# AugmentedStethoscope_v4.net
KiCad netlist of a schematic drawn in EAGLE
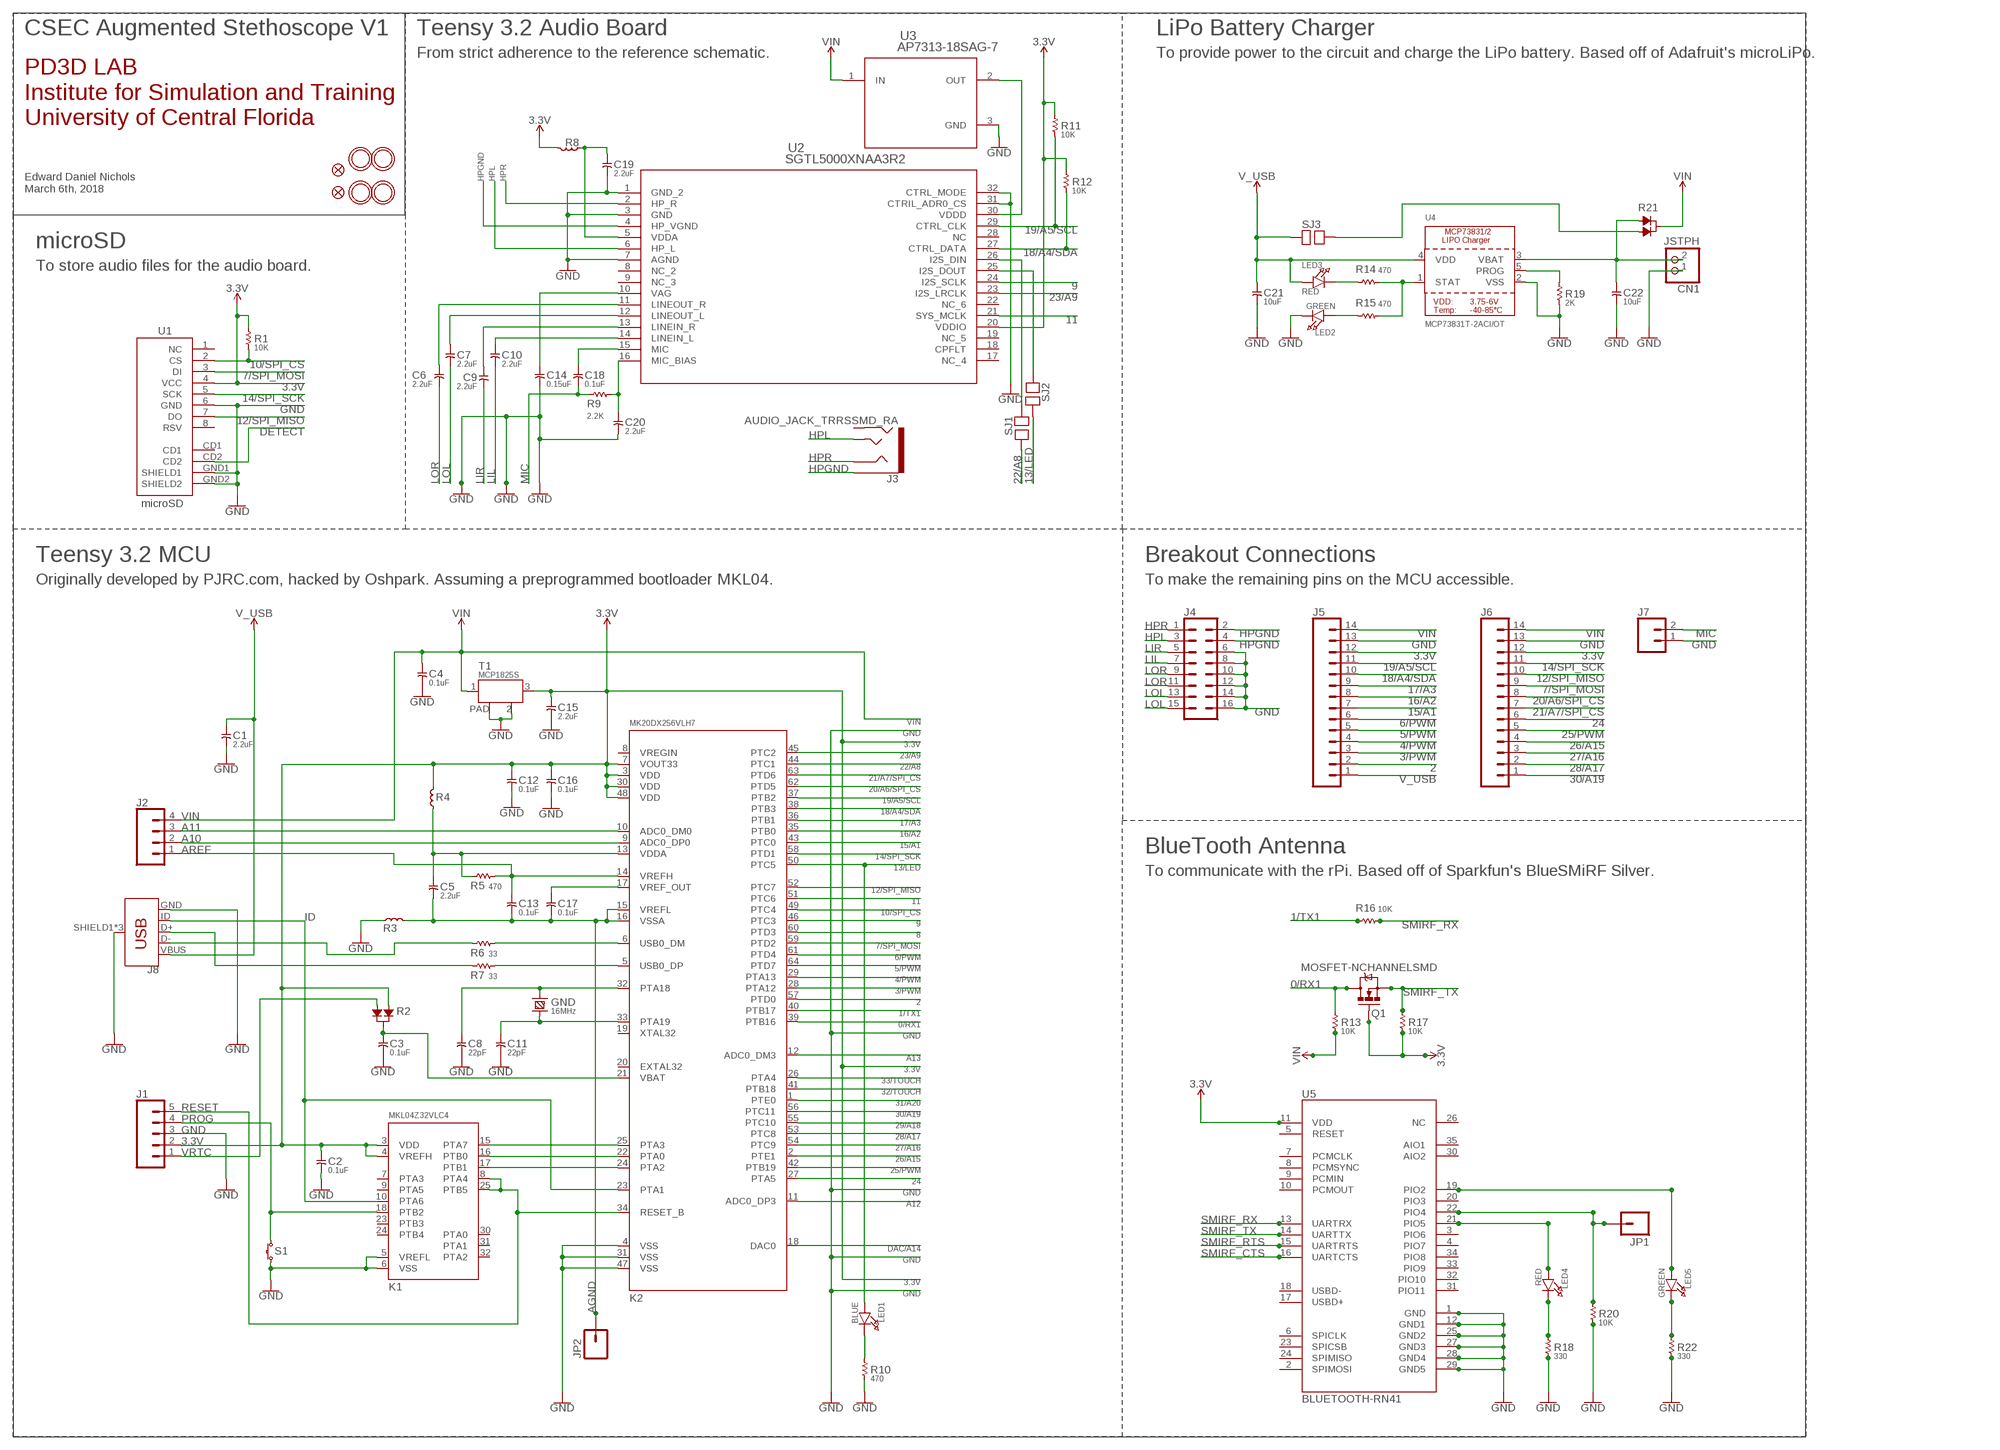
[diagram p0: schematic, sheet 1]

(export (version "E")
  (design (tool "Eeschema 10.0.6"))
  (components
    (comp (ref "C1")
      (value "2.2uF")
      (footprint "eagle-import:C0805")
      (fields (field (name "MF") "Taiyo Yuden") (field (name "MPN") "TMK212B7225KG-TR"))
      (libsource (lib "eagle-import") (part "CAPACITOR-2.2UF"))
    )
    (comp (ref "C2")
      (value "0.1uF")
      (footprint "eagle-import:C0603")
      (fields (field (name "MF") "Murata Electronics") (field (name "MPN") "GRM188R71C104KA01D"))
      (libsource (lib "eagle-import") (part "CAPACITOR-0.1UF"))
    )
    (comp (ref "C3")
      (value "0.1uF")
      (footprint "eagle-import:C0603")
      (fields (field (name "MF") "Murata Electronics") (field (name "MPN") "GRM188R71C104KA01D"))
      (libsource (lib "eagle-import") (part "CAPACITOR-0.1UF"))
    )
    (comp (ref "C4")
      (value "0.1uF")
      (footprint "eagle-import:C0603")
      (fields (field (name "MF") "Murata Electronics") (field (name "MPN") "GRM188R71C104KA01D"))
      (libsource (lib "eagle-import") (part "CAPACITOR-0.1UF"))
    )
    (comp (ref "C5")
      (value "2.2uF")
      (footprint "eagle-import:C0805")
      (fields (field (name "MF") "Taiyo Yuden") (field (name "MPN") "TMK212B7225KG-TR"))
      (libsource (lib "eagle-import") (part "CAPACITOR-2.2UF"))
    )
    (comp (ref "C6")
      (value "2.2uF")
      (footprint "eagle-import:C0805")
      (fields (field (name "MF") "Taiyo Yuden") (field (name "MPN") "TMK212B7225KG-TR"))
      (libsource (lib "eagle-import") (part "CAPACITOR-2.2UF"))
    )
    (comp (ref "C7")
      (value "2.2uF")
      (footprint "eagle-import:C0805")
      (fields (field (name "MF") "Taiyo Yuden") (field (name "MPN") "TMK212B7225KG-TR"))
      (libsource (lib "eagle-import") (part "CAPACITOR-2.2UF"))
    )
    (comp (ref "C8")
      (value "22pF")
      (footprint "eagle-import:C0603")
      (fields (field (name "MF") "Vishay / Vitramon") (field (name "MPN") "VJ0603A220JXACW1BC"))
      (libsource (lib "eagle-import") (part "CAPACITOR-22PF"))
    )
    (comp (ref "C9")
      (value "2.2uF")
      (footprint "eagle-import:C0805")
      (fields (field (name "MF") "Taiyo Yuden") (field (name "MPN") "TMK212B7225KG-TR"))
      (libsource (lib "eagle-import") (part "CAPACITOR-2.2UF"))
    )
    (comp (ref "C10")
      (value "2.2uF")
      (footprint "eagle-import:C0805")
      (fields (field (name "MF") "Taiyo Yuden") (field (name "MPN") "TMK212B7225KG-TR"))
      (libsource (lib "eagle-import") (part "CAPACITOR-2.2UF"))
    )
    (comp (ref "C11")
      (value "22pF")
      (footprint "eagle-import:C0603")
      (fields (field (name "MF") "Vishay / Vitramon") (field (name "MPN") "VJ0603A220JXACW1BC"))
      (libsource (lib "eagle-import") (part "CAPACITOR-22PF"))
    )
    (comp (ref "C12")
      (value "0.1uF")
      (footprint "eagle-import:C0603")
      (fields (field (name "MF") "Murata Electronics") (field (name "MPN") "GRM188R71C104KA01D"))
      (libsource (lib "eagle-import") (part "CAPACITOR-0.1UF"))
    )
    (comp (ref "C13")
      (value "0.1uF")
      (footprint "eagle-import:C0603")
      (fields (field (name "MF") "Murata Electronics") (field (name "MPN") "GRM188R71C104KA01D"))
      (libsource (lib "eagle-import") (part "CAPACITOR-0.1UF"))
    )
    (comp (ref "C14")
      (value "0.15uF")
      (footprint "eagle-import:C0805")
      (fields (field (name "MF") "Taiyo Yuden") (field (name "MPN") "TMK212B7225KG-TR"))
      (libsource (lib "eagle-import") (part "CAPACITOR-2.2UF"))
    )
    (comp (ref "C15")
      (value "2.2uF")
      (footprint "eagle-import:C0805")
      (fields (field (name "MF") "Taiyo Yuden") (field (name "MPN") "TMK212B7225KG-TR"))
      (libsource (lib "eagle-import") (part "CAPACITOR-2.2UF"))
    )
    (comp (ref "C16")
      (value "0.1uF")
      (footprint "eagle-import:C0603")
      (fields (field (name "MF") "Murata Electronics") (field (name "MPN") "GRM188R71C104KA01D"))
      (libsource (lib "eagle-import") (part "CAPACITOR-0.1UF"))
    )
    (comp (ref "C17")
      (value "0.1uF")
      (footprint "eagle-import:C0603")
      (fields (field (name "MF") "Murata Electronics") (field (name "MPN") "GRM188R71C104KA01D"))
      (libsource (lib "eagle-import") (part "CAPACITOR-0.1UF"))
    )
    (comp (ref "C18")
      (value "0.1uF")
      (footprint "eagle-import:C0805")
      (fields (field (name "MF") "Taiyo Yuden") (field (name "MPN") "TMK212B7225KG-TR"))
      (libsource (lib "eagle-import") (part "CAPACITOR-2.2UF"))
    )
    (comp (ref "C19")
      (value "2.2uF")
      (footprint "eagle-import:C0805")
      (fields (field (name "MF") "Taiyo Yuden") (field (name "MPN") "TMK212B7225KG-TR"))
      (libsource (lib "eagle-import") (part "CAPACITOR-2.2UF"))
    )
    (comp (ref "C20")
      (value "2.2uF")
      (footprint "eagle-import:C0805")
      (fields (field (name "MF") "Taiyo Yuden") (field (name "MPN") "TMK212B7225KG-TR"))
      (libsource (lib "eagle-import") (part "CAPACITOR-2.2UF"))
    )
    (comp (ref "C21")
      (value "10uF")
      (footprint "eagle-import:C0603")
      (fields (field (name "MF") "Murata Electronics") (field (name "MPN") "GRM188R71C104KA01D"))
      (libsource (lib "eagle-import") (part "CAPACITOR-0.1UF"))
    )
    (comp (ref "C22")
      (value "10uF")
      (footprint "eagle-import:C0603")
      (fields (field (name "MF") "Murata Electronics") (field (name "MPN") "GRM188R71C104KA01D"))
      (libsource (lib "eagle-import") (part "CAPACITOR-0.1UF"))
    )
    (comp (ref "CN1")
      (value "JSTPH")
      (footprint "eagle-import:JSTPH2")
      (libsource (lib "eagle-import") (part "JST_2PIN"))
    )
    (comp (ref "FID2")
      (value "FIDUCIAL\"\"")
      (footprint "eagle-import:FIDUCIAL_1MM")
      (libsource (lib "eagle-import") (part "FIDUCIAL{dblquote}{dblquote}"))
    )
    (comp (ref "FID3")
      (value "FIDUCIAL\"\"")
      (footprint "eagle-import:FIDUCIAL_1MM")
      (fields (field (name "BOM") "EXCLUDE"))
      (libsource (lib "eagle-import") (part "FIDUCIAL{dblquote}{dblquote}"))
    )
    (comp (ref "GND")
      (value "16MHz")
      (footprint "eagle-import:HC49US")
      (fields (field (name "MF") "ABRACON") (field (name "MPN") "ABL-16.000MHz-B1U"))
      (libsource (lib "eagle-import") (part "CRYSTAL-HC49US"))
    )
    (comp (ref "J1")
      (value "CONN_05")
      (footprint "eagle-import:1X05")
      (libsource (lib "eagle-import") (part "CONN_05"))
    )
    (comp (ref "J2")
      (value "CONN_04")
      (footprint "eagle-import:1X04")
      (libsource (lib "eagle-import") (part "CONN_04"))
    )
    (comp (ref "J3")
      (value "AUDIO_JACK_TRRSSMD_RA")
      (footprint "eagle-import:AUDIO_JACK_3.5MM_TRRS_SMD_RA")
      (libsource (lib "eagle-import") (part "AUDIO_JACK_TRRSSMD_RA"))
    )
    (comp (ref "J4")
      (value "CONN_08X2")
      (footprint "eagle-import:2X8")
      (libsource (lib "eagle-import") (part "CONN_08X2"))
    )
    (comp (ref "J5")
      (value "CONN_14")
      (footprint "eagle-import:1X14")
      (libsource (lib "eagle-import") (part "CONN_14"))
    )
    (comp (ref "J6")
      (value "CONN_14")
      (footprint "eagle-import:1X14")
      (libsource (lib "eagle-import") (part "CONN_14"))
    )
    (comp (ref "J7")
      (value "CONN_02")
      (footprint "eagle-import:1X02")
      (libsource (lib "eagle-import") (part "CONN_02"))
    )
    (comp (ref "J8")
      (value "USB_MICRO-B_FEMALE-SMT")
      (footprint "eagle-import:USB-B-MICRO-SMD")
      (libsource (lib "eagle-import") (part "USB_MICRO-B_FEMALE-SMT"))
    )
    (comp (ref "JP1")
      (value "M01SMDNS")
      (footprint "eagle-import:1X01NS")
      (libsource (lib "eagle-import") (part "M01SMDNS"))
    )
    (comp (ref "JP2")
      (value "M01SMDNS")
      (footprint "eagle-import:1X01NS")
      (libsource (lib "eagle-import") (part "M01SMDNS"))
    )
    (comp (ref "K1")
      (value "MKL04Z32VLC4")
      (footprint "eagle-import:LQFP32-08")
      (fields (field (name "MF") "PJRC") (field (name "MPN") "IC_MKL04Z32_TQFP32"))
      (libsource (lib "eagle-import") (part "MKL04Z32VLC4"))
    )
    (comp (ref "K2")
      (value "MK20DX256VLH7")
      (footprint "eagle-import:LQFP64-05")
      (fields (field (name "MF") "NXP"))
      (libsource (lib "eagle-import") (part "MK20DX256VLH7"))
    )
    (comp (ref "LED1")
      (value "BLUE")
      (footprint "eagle-import:CHIPLED_0805")
      (libsource (lib "eagle-import") (part "LED0805"))
    )
    (comp (ref "LED2")
      (value "GREEN")
      (footprint "eagle-import:CHIPLED_0805")
      (libsource (lib "eagle-import") (part "LED0805"))
    )
    (comp (ref "LED3")
      (value "RED")
      (footprint "eagle-import:CHIPLED_0805")
      (libsource (lib "eagle-import") (part "LED0805"))
    )
    (comp (ref "LED4")
      (value "RED")
      (footprint "eagle-import:CHIPLED_0805")
      (libsource (lib "eagle-import") (part "LED0805"))
    )
    (comp (ref "LED5")
      (value "GREEN")
      (footprint "eagle-import:CHIPLED_0805")
      (libsource (lib "eagle-import") (part "LED0805"))
    )
    (comp (ref "Q1")
      (value "MOSFET-NCHANNELSMD")
      (footprint "eagle-import:SOT23-3")
      (libsource (lib "eagle-import") (part "MOSFET-NCHANNELSMD"))
    )
    (comp (ref "R1")
      (value "10K")
      (footprint "eagle-import:R0603")
      (fields (field (name "MF") "Vishay") (field (name "MPN") "CRCW0603470RFKEA"))
      (libsource (lib "eagle-import") (part "RESISTOR-470R"))
    )
    (comp (ref "R2")
      (value "DIODE_DUAL")
      (footprint "eagle-import:SOT-23")
      (fields (field (name "MF") "NXP Semiconductors") (field (name "MPN") "BAT54C,215"))
      (libsource (lib "eagle-import") (part "DIODE_DUAL"))
    )
    (comp (ref "R3")
      (value "FERRITE")
      (footprint "eagle-import:L0603")
      (fields (field (name "MF") "Murata Electronics") (field (name "MPN") " BLM18AG601SN1D"))
      (libsource (lib "eagle-import") (part "FERRITE"))
    )
    (comp (ref "R4")
      (value "FERRITE")
      (footprint "eagle-import:L0603")
      (fields (field (name "MF") "Murata Electronics") (field (name "MPN") " BLM18AG601SN1D"))
      (libsource (lib "eagle-import") (part "FERRITE"))
    )
    (comp (ref "R5")
      (value "470")
      (footprint "eagle-import:R0603")
      (fields (field (name "MF") "Vishay") (field (name "MPN") "CRCW0603470RFKEA"))
      (libsource (lib "eagle-import") (part "RESISTOR-470R"))
    )
    (comp (ref "R6")
      (value "33")
      (footprint "eagle-import:R0603")
      (fields (field (name "MF") "Panasonic") (field (name "MPN") "ERJ-PA3F33R0V"))
      (libsource (lib "eagle-import") (part "RESISTOR-33R"))
    )
    (comp (ref "R7")
      (value "33")
      (footprint "eagle-import:R0603")
      (fields (field (name "MF") "Panasonic") (field (name "MPN") "ERJ-PA3F33R0V"))
      (libsource (lib "eagle-import") (part "RESISTOR-33R"))
    )
    (comp (ref "R8")
      (value "FERRITE")
      (footprint "eagle-import:L0603")
      (fields (field (name "MF") "Murata Electronics") (field (name "MPN") " BLM18AG601SN1D"))
      (libsource (lib "eagle-import") (part "FERRITE"))
    )
    (comp (ref "R9")
      (value "2.2K")
      (footprint "eagle-import:R0603")
      (fields (field (name "MF") "Vishay") (field (name "MPN") "CRCW0603470RFKEA"))
      (libsource (lib "eagle-import") (part "RESISTOR-470R"))
    )
    (comp (ref "R10")
      (value "470")
      (footprint "eagle-import:R0603")
      (fields (field (name "MF") "Vishay") (field (name "MPN") "CRCW0603470RFKEA"))
      (libsource (lib "eagle-import") (part "RESISTOR-470R"))
    )
    (comp (ref "R11")
      (value "10K")
      (footprint "eagle-import:R0603")
      (fields (field (name "MF") "Vishay") (field (name "MPN") "CRCW0603470RFKEA"))
      (libsource (lib "eagle-import") (part "RESISTOR-470R"))
    )
    (comp (ref "R12")
      (value "10K")
      (footprint "eagle-import:R0603")
      (fields (field (name "MF") "Vishay") (field (name "MPN") "CRCW0603470RFKEA"))
      (libsource (lib "eagle-import") (part "RESISTOR-470R"))
    )
    (comp (ref "R13")
      (value "10K")
      (footprint "eagle-import:R0603")
      (fields (field (name "MF") "Vishay") (field (name "MPN") "CRCW0603470RFKEA"))
      (libsource (lib "eagle-import") (part "RESISTOR-470R"))
    )
    (comp (ref "R14")
      (value "470")
      (footprint "eagle-import:R0603")
      (fields (field (name "MF") "Panasonic") (field (name "MPN") "ERJ-PA3F33R0V"))
      (libsource (lib "eagle-import") (part "RESISTOR-33R"))
    )
    (comp (ref "R15")
      (value "470")
      (footprint "eagle-import:R0603")
      (fields (field (name "MF") "Panasonic") (field (name "MPN") "ERJ-PA3F33R0V"))
      (libsource (lib "eagle-import") (part "RESISTOR-33R"))
    )
    (comp (ref "R16")
      (value "10K")
      (footprint "eagle-import:R0603")
      (fields (field (name "MF") "Panasonic") (field (name "MPN") "ERJ-PA3F33R0V"))
      (libsource (lib "eagle-import") (part "RESISTOR-33R"))
    )
    (comp (ref "R17")
      (value "10K")
      (footprint "eagle-import:R0603")
      (fields (field (name "MF") "Vishay") (field (name "MPN") "CRCW0603470RFKEA"))
      (libsource (lib "eagle-import") (part "RESISTOR-470R"))
    )
    (comp (ref "R18")
      (value "330")
      (footprint "eagle-import:R0603")
      (fields (field (name "MF") "Vishay") (field (name "MPN") "CRCW0603470RFKEA"))
      (libsource (lib "eagle-import") (part "RESISTOR-470R"))
    )
    (comp (ref "R19")
      (value "2K")
      (footprint "eagle-import:R0603")
      (fields (field (name "MF") "Vishay") (field (name "MPN") "CRCW0603470RFKEA"))
      (libsource (lib "eagle-import") (part "RESISTOR-470R"))
    )
    (comp (ref "R20")
      (value "10K")
      (footprint "eagle-import:R0603")
      (fields (field (name "MF") "Vishay") (field (name "MPN") "CRCW0603470RFKEA"))
      (libsource (lib "eagle-import") (part "RESISTOR-470R"))
    )
    (comp (ref "R21")
      (value "DIODE_DUAL")
      (footprint "eagle-import:SOT-23")
      (fields (field (name "MF") "NXP Semiconductors") (field (name "MPN") "BAT54C,215"))
      (libsource (lib "eagle-import") (part "DIODE_DUAL"))
    )
    (comp (ref "R22")
      (value "330")
      (footprint "eagle-import:R0603")
      (fields (field (name "MF") "Vishay") (field (name "MPN") "CRCW0603470RFKEA"))
      (libsource (lib "eagle-import") (part "RESISTOR-470R"))
    )
    (comp (ref "S1")
      (value "TACT_SWITCH")
      (footprint "eagle-import:ALPS_SKHH")
      (fields (field (name "MF") "ALPS") (field (name "MPN") "SKHHPKA010"))
      (libsource (lib "eagle-import") (part "TACT_SWITCH"))
    )
    (comp (ref "SJ1")
      (value "SOLDERJUMPER")
      (footprint "eagle-import:SOLDERJUMPER")
      (libsource (lib "eagle-import") (part "SOLDERJUMPER"))
    )
    (comp (ref "SJ2")
      (value "SOLDERJUMPER")
      (footprint "eagle-import:SOLDERJUMPER")
      (libsource (lib "eagle-import") (part "SOLDERJUMPER"))
    )
    (comp (ref "SJ3")
      (value "SOLDERJUMPER")
      (footprint "eagle-import:SOLDERJUMPER")
      (libsource (lib "eagle-import") (part "SOLDERJUMPER"))
    )
    (comp (ref "T1")
      (value "MCP1825S")
      (footprint "eagle-import:SOT-223")
      (fields (field (name "MF") "Microchip Technology") (field (name "MPN") "MCP1825S-3302E/DB"))
      (libsource (lib "eagle-import") (part "LDO"))
    )
    (comp (ref "U$1")
      (value "MOUNTINGHOLE2.5")
      (footprint "eagle-import:MOUNTINGHOLE_2.5_PLATED")
      (libsource (lib "eagle-import") (part "MOUNTINGHOLE2.5"))
    )
    (comp (ref "U$15")
      (value "MOUNTINGHOLE2.5")
      (footprint "eagle-import:MOUNTINGHOLE_2.5_PLATED")
      (libsource (lib "eagle-import") (part "MOUNTINGHOLE2.5"))
    )
    (comp (ref "U$17")
      (value "MOUNTINGHOLE2.5")
      (footprint "eagle-import:MOUNTINGHOLE_2.5_PLATED")
      (libsource (lib "eagle-import") (part "MOUNTINGHOLE2.5"))
    )
    (comp (ref "U$18")
      (value "MOUNTINGHOLE2.5")
      (footprint "eagle-import:MOUNTINGHOLE_2.5_PLATED")
      (libsource (lib "eagle-import") (part "MOUNTINGHOLE2.5"))
    )
    (comp (ref "U1")
      (value "microSD")
      (footprint "eagle-import:MICRO-SD-SOCKET-PP")
      (libsource (lib "eagle-import") (part "USD-SOCKETSMD"))
    )
    (comp (ref "U2")
      (value "SGTL5000XNAA3R2")
      (footprint "eagle-import:QFN32")
      (libsource (lib "eagle-import") (part "SGTL5000XNAA3R2"))
    )
    (comp (ref "U3")
      (value "AP7313-18SAG-7")
      (footprint "eagle-import:SOT-23")
      (fields (field (name "MANUFACTURER_PART_NUMBER") "AP731318SAG7"))
      (libsource (lib "eagle-import") (part "AP7313-18SAG-7"))
    )
    (comp (ref "U4")
      (value "MCP73831T-2ACI/OT")
      (footprint "eagle-import:SOT23-5")
      (libsource (lib "eagle-import") (part "MCP73831/2"))
    )
    (comp (ref "U5")
      (value "BLUETOOTH-RN41")
      (footprint "eagle-import:RN41")
      (libsource (lib "eagle-import") (part "BLUETOOTH-RN41{dblquote}"))
    )
  )
  (nets
    (net (code "1") (name "/0{slash}RX1") (class "Default")
      (node (ref "K2") (pin "39") (pinfunction "PTB16_39") (pintype "bidirectional"))
      (node (ref "Q1") (pin "3") (pinfunction "D_3") (pintype "passive"))
      (node (ref "R13") (pin "2") (pinfunction "2_2") (pintype "passive"))
    )
    (net (code "2") (name "/1{slash}TX1") (class "Default")
      (node (ref "K2") (pin "40") (pinfunction "PTB17_40") (pintype "bidirectional"))
      (node (ref "R16") (pin "1") (pinfunction "1_1") (pintype "passive"))
    )
    (net (code "3") (name "/2") (class "Default")
      (node (ref "J5") (pin "2") (pinfunction "2_2") (pintype "passive"))
      (node (ref "K2") (pin "57") (pinfunction "PTD0_57") (pintype "bidirectional"))
    )
    (net (code "4") (name "/3{slash}PWM") (class "Default")
      (node (ref "J5") (pin "3") (pinfunction "3_3") (pintype "passive"))
      (node (ref "K2") (pin "28") (pinfunction "PTA12_28") (pintype "bidirectional"))
    )
    (net (code "5") (name "/4{slash}PWM") (class "Default")
      (node (ref "J5") (pin "4") (pinfunction "4_4") (pintype "passive"))
      (node (ref "K2") (pin "29") (pinfunction "PTA13_29") (pintype "bidirectional"))
    )
    (net (code "6") (name "/5{slash}PWM") (class "Default")
      (node (ref "J5") (pin "5") (pinfunction "5_5") (pintype "passive"))
      (node (ref "K2") (pin "64") (pinfunction "PTD7_64") (pintype "bidirectional"))
    )
    (net (code "7") (name "/6{slash}PWM") (class "Default")
      (node (ref "J5") (pin "6") (pinfunction "6_6") (pintype "passive"))
      (node (ref "K2") (pin "61") (pinfunction "PTD4_61") (pintype "bidirectional"))
    )
    (net (code "8") (name "/7{slash}SPI_MOSI") (class "Default")
      (node (ref "J6") (pin "9") (pinfunction "9_9") (pintype "passive"))
      (node (ref "K2") (pin "59") (pinfunction "PTD2_59") (pintype "bidirectional"))
      (node (ref "U1") (pin "3") (pinfunction "DI_3") (pintype "bidirectional"))
    )
    (net (code "9") (name "/8") (class "Default")
      (node (ref "K2") (pin "60") (pinfunction "PTD3_60") (pintype "bidirectional"))
    )
    (net (code "10") (name "/9") (class "Default")
      (node (ref "K2") (pin "46") (pinfunction "PTC3_46") (pintype "bidirectional"))
      (node (ref "U2") (pin "24") (pinfunction "I2S_SCLK_24") (pintype "passive"))
    )
    (net (code "11") (name "/10{slash}SPI_CS") (class "Default")
      (node (ref "K2") (pin "49") (pinfunction "PTC4_49") (pintype "bidirectional"))
      (node (ref "R1") (pin "1") (pinfunction "1_1") (pintype "passive"))
      (node (ref "U1") (pin "2") (pinfunction "CS_2") (pintype "bidirectional"))
    )
    (net (code "12") (name "/11") (class "Default")
      (node (ref "K2") (pin "51") (pinfunction "PTC6_51") (pintype "bidirectional"))
      (node (ref "U2") (pin "21") (pinfunction "SYS_MCLK_21") (pintype "passive"))
    )
    (net (code "13") (name "/12{slash}SPI_MISO") (class "Default")
      (node (ref "J6") (pin "10") (pinfunction "10_10") (pintype "passive"))
      (node (ref "K2") (pin "52") (pinfunction "PTC7_52") (pintype "bidirectional"))
      (node (ref "U1") (pin "7") (pinfunction "DO_7") (pintype "bidirectional"))
    )
    (net (code "14") (name "/13{slash}LED") (class "Default")
      (node (ref "K2") (pin "50") (pinfunction "PTC5_50") (pintype "bidirectional"))
      (node (ref "LED1") (pin "A") (pinfunction "A_A") (pintype "passive"))
      (node (ref "SJ2") (pin "2") (pinfunction "2_2") (pintype "passive"))
    )
    (net (code "15") (name "/14{slash}SPI_SCK") (class "Default")
      (node (ref "J6") (pin "11") (pinfunction "11_11") (pintype "passive"))
      (node (ref "K2") (pin "58") (pinfunction "PTD1_58") (pintype "bidirectional"))
      (node (ref "U1") (pin "5") (pinfunction "SCK_5") (pintype "bidirectional"))
    )
    (net (code "16") (name "/15{slash}A1") (class "Default")
      (node (ref "J5") (pin "7") (pinfunction "7_7") (pintype "passive"))
      (node (ref "K2") (pin "43") (pinfunction "PTC0_43") (pintype "bidirectional"))
    )
    (net (code "17") (name "/16{slash}A2") (class "Default")
      (node (ref "J5") (pin "8") (pinfunction "8_8") (pintype "passive"))
      (node (ref "K2") (pin "35") (pinfunction "PTB0_35") (pintype "bidirectional"))
    )
    (net (code "18") (name "/17{slash}A3") (class "Default")
      (node (ref "J5") (pin "9") (pinfunction "9_9") (pintype "passive"))
      (node (ref "K2") (pin "36") (pinfunction "PTB1_36") (pintype "bidirectional"))
    )
    (net (code "19") (name "/18{slash}A4{slash}SDA") (class "Default")
      (node (ref "J5") (pin "10") (pinfunction "10_10") (pintype "passive"))
      (node (ref "K2") (pin "38") (pinfunction "PTB3_38") (pintype "bidirectional"))
      (node (ref "R12") (pin "1") (pinfunction "1_1") (pintype "passive"))
      (node (ref "U2") (pin "27") (pinfunction "CTRL_DATA_27") (pintype "passive"))
    )
    (net (code "20") (name "/19{slash}A5{slash}SCL") (class "Default")
      (node (ref "J5") (pin "11") (pinfunction "11_11") (pintype "passive"))
      (node (ref "K2") (pin "37") (pinfunction "PTB2_37") (pintype "bidirectional"))
      (node (ref "R11") (pin "1") (pinfunction "1_1") (pintype "passive"))
      (node (ref "U2") (pin "29") (pinfunction "CTRL_CLK_29") (pintype "passive"))
    )
    (net (code "21") (name "/20{slash}A6{slash}SPI_CS") (class "Default")
      (node (ref "J6") (pin "8") (pinfunction "8_8") (pintype "passive"))
      (node (ref "K2") (pin "62") (pinfunction "PTD5_62") (pintype "bidirectional"))
    )
    (net (code "22") (name "/21{slash}A7{slash}SPI_CS") (class "Default")
      (node (ref "J6") (pin "7") (pinfunction "7_7") (pintype "passive"))
      (node (ref "K2") (pin "63") (pinfunction "PTD6_63") (pintype "bidirectional"))
    )
    (net (code "23") (name "/22{slash}A8") (class "Default")
      (node (ref "K2") (pin "44") (pinfunction "PTC1_44") (pintype "bidirectional"))
      (node (ref "SJ1") (pin "2") (pinfunction "2_2") (pintype "passive"))
    )
    (net (code "24") (name "/23{slash}A9") (class "Default")
      (node (ref "K2") (pin "45") (pinfunction "PTC2_45") (pintype "bidirectional"))
      (node (ref "U2") (pin "23") (pinfunction "I2S_LRCLK_23") (pintype "passive"))
    )
    (net (code "25") (name "/24") (class "Default")
      (node (ref "J6") (pin "6") (pinfunction "6_6") (pintype "passive"))
      (node (ref "K2") (pin "27") (pinfunction "PTA5_27") (pintype "bidirectional"))
    )
    (net (code "26") (name "/25{slash}PWM") (class "Default")
      (node (ref "J6") (pin "5") (pinfunction "5_5") (pintype "passive"))
      (node (ref "K2") (pin "42") (pinfunction "PTB19_42") (pintype "bidirectional"))
    )
    (net (code "27") (name "/26{slash}A15") (class "Default")
      (node (ref "J6") (pin "4") (pinfunction "4_4") (pintype "passive"))
      (node (ref "K2") (pin "2") (pinfunction "PTE1_2") (pintype "bidirectional"))
    )
    (net (code "28") (name "/27{slash}A16") (class "Default")
      (node (ref "J6") (pin "3") (pinfunction "3_3") (pintype "passive"))
      (node (ref "K2") (pin "54") (pinfunction "PTC9_54") (pintype "bidirectional"))
    )
    (net (code "29") (name "/28{slash}A17") (class "Default")
      (node (ref "J6") (pin "2") (pinfunction "2_2") (pintype "passive"))
      (node (ref "K2") (pin "53") (pinfunction "PTC8_53") (pintype "bidirectional"))
    )
    (net (code "30") (name "/29{slash}A18") (class "Default")
      (node (ref "K2") (pin "55") (pinfunction "PTC10_55") (pintype "bidirectional"))
    )
    (net (code "31") (name "/30{slash}A19") (class "Default")
      (node (ref "J6") (pin "1") (pinfunction "1_1") (pintype "passive"))
      (node (ref "K2") (pin "56") (pinfunction "PTC11_56") (pintype "bidirectional"))
    )
    (net (code "32") (name "/31{slash}A20") (class "Default")
      (node (ref "K2") (pin "1") (pinfunction "PTE0_1") (pintype "bidirectional"))
    )
    (net (code "33") (name "/32{slash}TOUCH") (class "Default")
      (node (ref "K2") (pin "41") (pinfunction "PTB18_41") (pintype "bidirectional"))
    )
    (net (code "34") (name "/33{slash}TOUCH") (class "Default")
      (node (ref "K2") (pin "26") (pinfunction "PTA4_26") (pintype "bidirectional"))
    )
    (net (code "35") (name "/A10") (class "Default")
      (node (ref "J2") (pin "2") (pinfunction "2_2") (pintype "passive"))
      (node (ref "K2") (pin "9") (pinfunction "ADC0_DP0_9") (pintype "bidirectional"))
    )
    (net (code "36") (name "/A11") (class "Default")
      (node (ref "J2") (pin "3") (pinfunction "3_3") (pintype "passive"))
      (node (ref "K2") (pin "10") (pinfunction "ADC0_DM0_10") (pintype "bidirectional"))
    )
    (net (code "37") (name "/A12") (class "Default")
      (node (ref "K2") (pin "11") (pinfunction "ADC0_DP3_11") (pintype "bidirectional"))
    )
    (net (code "38") (name "/A13") (class "Default")
      (node (ref "K2") (pin "12") (pinfunction "ADC0_DM3_12") (pintype "bidirectional"))
    )
    (net (code "39") (name "/AGND") (class "Default")
      (node (ref "C13") (pin "2") (pinfunction "2_2") (pintype "passive"))
      (node (ref "C17") (pin "2") (pinfunction "2_2") (pintype "passive"))
      (node (ref "C5") (pin "2") (pinfunction "2_2") (pintype "passive"))
      (node (ref "JP2") (pin "1") (pinfunction "1_1") (pintype "passive"))
      (node (ref "K2") (pin "15") (pinfunction "VREFL_15") (pintype "bidirectional"))
      (node (ref "K2") (pin "16") (pinfunction "VSSA_16") (pintype "bidirectional"))
      (node (ref "R3") (pin "2") (pinfunction "2_2") (pintype "passive"))
    )
    (net (code "40") (name "/AREF") (class "Default")
      (node (ref "C13") (pin "1") (pinfunction "1_1") (pintype "passive"))
      (node (ref "J2") (pin "1") (pinfunction "1_1") (pintype "passive"))
      (node (ref "K2") (pin "14") (pinfunction "VREFH_14") (pintype "bidirectional"))
      (node (ref "R5") (pin "2") (pinfunction "2_2") (pintype "passive"))
    )
    (net (code "41") (name "/DAC{slash}A14") (class "Default")
      (node (ref "K2") (pin "18") (pinfunction "DAC0_18") (pintype "bidirectional"))
    )
    (net (code "42") (name "/DETECT") (class "Default")
      (node (ref "U1") (pin "CD2") (pinfunction "CD2_CD2") (pintype "bidirectional"))
    )
    (net (code "43") (name "/HPGND") (class "Default")
      (node (ref "J3") (pin "EARTH") (pinfunction "EARTH_EARTH") (pintype "bidirectional"))
      (node (ref "J4") (pin "2") (pinfunction "2_2") (pintype "passive"))
      (node (ref "J4") (pin "4") (pinfunction "4_4") (pintype "passive"))
      (node (ref "U2") (pin "4") (pinfunction "HP_VGND_4") (pintype "power_in"))
    )
    (net (code "44") (name "/HPL") (class "Default")
      (node (ref "J3") (pin "TIP") (pinfunction "TIP_TIP") (pintype "bidirectional"))
      (node (ref "J4") (pin "3") (pinfunction "3_3") (pintype "passive"))
      (node (ref "U2") (pin "6") (pinfunction "HP_L_6") (pintype "output"))
    )
    (net (code "45") (name "/HPR") (class "Default")
      (node (ref "J3") (pin "RING1") (pinfunction "RING1_RING1") (pintype "bidirectional"))
      (node (ref "J4") (pin "1") (pinfunction "1_1") (pintype "passive"))
      (node (ref "U2") (pin "2") (pinfunction "HP_R_2") (pintype "output"))
    )
    (net (code "46") (name "/ID") (class "Default")
      (node (ref "J8") (pin "ID") (pinfunction "ID_ID") (pintype "bidirectional"))
      (node (ref "K1") (pin "10") (pinfunction "PTA6_10") (pintype "bidirectional"))
      (node (ref "K2") (pin "23") (pinfunction "PTA1_23") (pintype "bidirectional"))
    )
    (net (code "47") (name "/LIL") (class "Default")
      (node (ref "C10") (pin "2") (pinfunction "2_2") (pintype "passive"))
      (node (ref "J4") (pin "7") (pinfunction "7_7") (pintype "passive"))
    )
    (net (code "48") (name "/LIR") (class "Default")
      (node (ref "C9") (pin "2") (pinfunction "2_2") (pintype "passive"))
      (node (ref "J4") (pin "5") (pinfunction "5_5") (pintype "passive"))
    )
    (net (code "49") (name "/LOL") (class "Default")
      (node (ref "C7") (pin "2") (pinfunction "2_2") (pintype "passive"))
      (node (ref "J4") (pin "13") (pinfunction "13_13") (pintype "passive"))
      (node (ref "J4") (pin "15") (pinfunction "15_15") (pintype "passive"))
    )
    (net (code "50") (name "/LOR") (class "Default")
      (node (ref "C6") (pin "2") (pinfunction "2_2") (pintype "passive"))
      (node (ref "J4") (pin "11") (pinfunction "11_11") (pintype "passive"))
      (node (ref "J4") (pin "9") (pinfunction "9_9") (pintype "passive"))
    )
    (net (code "51") (name "/MIC") (class "Default")
      (node (ref "C18") (pin "2") (pinfunction "2_2") (pintype "passive"))
      (node (ref "J7") (pin "2") (pinfunction "2_2") (pintype "passive"))
      (node (ref "R9") (pin "1") (pinfunction "1_1") (pintype "passive"))
    )
    (net (code "52") (name "/PROG") (class "Default")
      (node (ref "J1") (pin "4") (pinfunction "4_4") (pintype "passive"))
      (node (ref "K1") (pin "18") (pinfunction "PTB2_18") (pintype "bidirectional"))
      (node (ref "S1") (pin "1") (pinfunction "1_1") (pintype "passive"))
      (node (ref "S1") (pin "2") (pinfunction "1_2") (pintype "passive"))
    )
    (net (code "53") (name "/RESET") (class "Default")
      (node (ref "J1") (pin "5") (pinfunction "5_5") (pintype "passive"))
      (node (ref "K1") (pin "25") (pinfunction "PTB5_25") (pintype "bidirectional"))
      (node (ref "K1") (pin "8") (pinfunction "PTA4_8") (pintype "bidirectional"))
      (node (ref "K2") (pin "34") (pinfunction "RESET_B_34") (pintype "bidirectional"))
    )
    (net (code "54") (name "/SMIRF_CTS") (class "Default")
      (node (ref "U5") (pin "16") (pinfunction "UARTCTS_16") (pintype "bidirectional"))
    )
    (net (code "55") (name "/SMIRF_RTS") (class "Default")
      (node (ref "U5") (pin "15") (pinfunction "UARTRTS_15") (pintype "bidirectional"))
    )
    (net (code "56") (name "/SMIRF_RX") (class "Default")
      (node (ref "R16") (pin "2") (pinfunction "2_2") (pintype "passive"))
      (node (ref "U5") (pin "13") (pinfunction "UARTRX_13") (pintype "bidirectional"))
    )
    (net (code "57") (name "/SMIRF_TX") (class "Default")
      (node (ref "Q1") (pin "2") (pinfunction "S_2") (pintype "passive"))
      (node (ref "R17") (pin "2") (pinfunction "2_2") (pintype "passive"))
      (node (ref "U5") (pin "14") (pinfunction "UARTTX_14") (pintype "bidirectional"))
    )
    (net (code "58") (name "/VRTC") (class "Default")
      (node (ref "J1") (pin "1") (pinfunction "1_1") (pintype "passive"))
      (node (ref "R2") (pin "2") (pinfunction "2_2") (pintype "bidirectional"))
    )
    (net (code "59") (name "3.3V") (class "Default")
      (node (ref "C12") (pin "1") (pinfunction "1_1") (pintype "passive"))
      (node (ref "C15") (pin "1") (pinfunction "1_1") (pintype "passive"))
      (node (ref "C16") (pin "1") (pinfunction "1_1") (pintype "passive"))
      (node (ref "C2") (pin "1") (pinfunction "1_1") (pintype "passive"))
      (node (ref "J1") (pin "2") (pinfunction "2_2") (pintype "passive"))
      (node (ref "J5") (pin "12") (pinfunction "12_12") (pintype "passive"))
      (node (ref "J6") (pin "12") (pinfunction "12_12") (pintype "passive"))
      (node (ref "K1") (pin "3") (pinfunction "VDD_3") (pintype "bidirectional"))
      (node (ref "K1") (pin "4") (pinfunction "VREFH_4") (pintype "bidirectional"))
      (node (ref "K2") (pin "3") (pinfunction "VDD_3") (pintype "bidirectional"))
      (node (ref "K2") (pin "30") (pinfunction "VDD_30") (pintype "bidirectional"))
      (node (ref "K2") (pin "48") (pinfunction "VDD_48") (pintype "bidirectional"))
      (node (ref "K2") (pin "7") (pinfunction "VOUT33_7") (pintype "bidirectional"))
      (node (ref "Q1") (pin "1") (pinfunction "G_1") (pintype "passive"))
      (node (ref "R1") (pin "2") (pinfunction "2_2") (pintype "passive"))
      (node (ref "R11") (pin "2") (pinfunction "2_2") (pintype "passive"))
      (node (ref "R12") (pin "2") (pinfunction "2_2") (pintype "passive"))
      (node (ref "R17") (pin "1") (pinfunction "1_1") (pintype "passive"))
      (node (ref "R2") (pin "1") (pinfunction "1_1") (pintype "bidirectional"))
      (node (ref "R4") (pin "2") (pinfunction "2_2") (pintype "passive"))
      (node (ref "R8") (pin "2") (pinfunction "2_2") (pintype "passive"))
      (node (ref "T1") (pin "3") (pinfunction "OUT_3") (pintype "bidirectional"))
      (node (ref "U1") (pin "4") (pinfunction "VCC_4") (pintype "bidirectional"))
      (node (ref "U2") (pin "20") (pinfunction "VDDIO_20") (pintype "power_in"))
      (node (ref "U5") (pin "11") (pinfunction "VDD_11") (pintype "bidirectional"))
    )
    (net (code "60") (name "GND") (class "Default")
      (node (ref "C1") (pin "2") (pinfunction "2_2") (pintype "passive"))
      (node (ref "C11") (pin "2") (pinfunction "2_2") (pintype "passive"))
      (node (ref "C12") (pin "2") (pinfunction "2_2") (pintype "passive"))
      (node (ref "C14") (pin "2") (pinfunction "2_2") (pintype "passive"))
      (node (ref "C15") (pin "2") (pinfunction "2_2") (pintype "passive"))
      (node (ref "C16") (pin "2") (pinfunction "2_2") (pintype "passive"))
      (node (ref "C19") (pin "2") (pinfunction "2_2") (pintype "passive"))
      (node (ref "C2") (pin "2") (pinfunction "2_2") (pintype "passive"))
      (node (ref "C20") (pin "2") (pinfunction "2_2") (pintype "passive"))
      (node (ref "C21") (pin "2") (pinfunction "2_2") (pintype "passive"))
      (node (ref "C22") (pin "2") (pinfunction "2_2") (pintype "passive"))
      (node (ref "C3") (pin "2") (pinfunction "2_2") (pintype "passive"))
      (node (ref "C4") (pin "2") (pinfunction "2_2") (pintype "passive"))
      (node (ref "C8") (pin "2") (pinfunction "2_2") (pintype "passive"))
      (node (ref "CN1") (pin "1") (pinfunction "1_1") (pintype "passive"))
      (node (ref "J1") (pin "3") (pinfunction "3_3") (pintype "passive"))
      (node (ref "J4") (pin "10") (pinfunction "10_10") (pintype "passive"))
      (node (ref "J4") (pin "12") (pinfunction "12_12") (pintype "passive"))
      (node (ref "J4") (pin "14") (pinfunction "14_14") (pintype "passive"))
      (node (ref "J4") (pin "16") (pinfunction "16_16") (pintype "passive"))
      (node (ref "J4") (pin "6") (pinfunction "6_6") (pintype "passive"))
      (node (ref "J4") (pin "8") (pinfunction "8_8") (pintype "passive"))
      (node (ref "J5") (pin "13") (pinfunction "13_13") (pintype "passive"))
      (node (ref "J6") (pin "13") (pinfunction "13_13") (pintype "passive"))
      (node (ref "J7") (pin "1") (pinfunction "1_1") (pintype "passive"))
      (node (ref "J8") (pin "GND") (pinfunction "GND_GND") (pintype "power_in"))
      (node (ref "J8") (pin "SHIELD1") (pinfunction "SHIELD_SHIELD1") (pintype "bidirectional"))
      (node (ref "J8") (pin "SHIELD2") (pinfunction "SHIELD_SHIELD2") (pintype "bidirectional"))
      (node (ref "J8") (pin "SHIELD3") (pinfunction "SHIELD_SHIELD3") (pintype "bidirectional"))
      (node (ref "K1") (pin "5") (pinfunction "VREFL_5") (pintype "bidirectional"))
      (node (ref "K1") (pin "6") (pinfunction "VSS_6") (pintype "bidirectional"))
      (node (ref "K2") (pin "31") (pinfunction "VSS_31") (pintype "bidirectional"))
      (node (ref "K2") (pin "4") (pinfunction "VSS_4") (pintype "bidirectional"))
      (node (ref "K2") (pin "47") (pinfunction "VSS_47") (pintype "bidirectional"))
      (node (ref "LED2") (pin "C") (pinfunction "C_C") (pintype "passive"))
      (node (ref "R10") (pin "1") (pinfunction "1_1") (pintype "passive"))
      (node (ref "R18") (pin "1") (pinfunction "1_1") (pintype "passive"))
      (node (ref "R19") (pin "1") (pinfunction "1_1") (pintype "passive"))
      (node (ref "R20") (pin "1") (pinfunction "1_1") (pintype "passive"))
      (node (ref "R22") (pin "1") (pinfunction "1_1") (pintype "passive"))
      (node (ref "R3") (pin "1") (pinfunction "1_1") (pintype "passive"))
      (node (ref "S1") (pin "3") (pinfunction "3_3") (pintype "passive"))
      (node (ref "S1") (pin "4") (pinfunction "3_4") (pintype "passive"))
      (node (ref "T1") (pin "2") (pinfunction "GND_2") (pintype "bidirectional"))
      (node (ref "T1") (pin "PAD") (pinfunction "PAD_PAD") (pintype "bidirectional"))
      (node (ref "U1") (pin "6") (pinfunction "GND_6") (pintype "bidirectional"))
      (node (ref "U1") (pin "GND1") (pinfunction "SHIELD1_GND1") (pintype "bidirectional"))
      (node (ref "U1") (pin "GND2") (pinfunction "SHIELD2_GND2") (pintype "bidirectional"))
      (node (ref "U2") (pin "1") (pinfunction "GND_2_1") (pintype "power_in"))
      (node (ref "U2") (pin "3") (pinfunction "GND_3") (pintype "power_in"))
      (node (ref "U2") (pin "31") (pinfunction "CTRIL_ADR0_CS_31") (pintype "passive"))
      (node (ref "U2") (pin "32") (pinfunction "CTRL_MODE_32") (pintype "passive"))
      (node (ref "U2") (pin "7") (pinfunction "AGND_7") (pintype "power_in"))
      (node (ref "U3") (pin "3") (pinfunction "GND_3") (pintype "power_in"))
      (node (ref "U4") (pin "2") (pinfunction "VSS_2") (pintype "power_in"))
      (node (ref "U5") (pin "1") (pinfunction "GND_1") (pintype "bidirectional"))
      (node (ref "U5") (pin "12") (pinfunction "GND1_12") (pintype "bidirectional"))
      (node (ref "U5") (pin "25") (pinfunction "GND2_25") (pintype "bidirectional"))
      (node (ref "U5") (pin "27") (pinfunction "GND3_27") (pintype "bidirectional"))
      (node (ref "U5") (pin "28") (pinfunction "GND4_28") (pintype "bidirectional"))
      (node (ref "U5") (pin "29") (pinfunction "GND5_29") (pintype "bidirectional"))
    )
    (net (code "61") (name "Net-(J8-PadD+)") (class "Default")
      (node (ref "J8") (pin "D+") (pinfunction "D+_D+") (pintype "bidirectional"))
      (node (ref "R7") (pin "1") (pinfunction "1_1") (pintype "passive"))
    )
    (net (code "62") (name "Net-(J8-PadD-)") (class "Default")
      (node (ref "J8") (pin "D-") (pinfunction "D-_D-") (pintype "bidirectional"))
      (node (ref "R6") (pin "1") (pinfunction "1_1") (pintype "passive"))
    )
    (net (code "63") (name "Net-(K1-PTA7)") (class "Default")
      (node (ref "K1") (pin "15") (pinfunction "PTA7_15") (pintype "bidirectional"))
      (node (ref "K2") (pin "25") (pinfunction "PTA3_25") (pintype "bidirectional"))
    )
    (net (code "64") (name "Net-(K1-PTB0)") (class "Default")
      (node (ref "K1") (pin "16") (pinfunction "PTB0_16") (pintype "bidirectional"))
      (node (ref "K2") (pin "22") (pinfunction "PTA0_22") (pintype "bidirectional"))
    )
    (net (code "65") (name "Net-(K1-PTB1)") (class "Default")
      (node (ref "K1") (pin "17") (pinfunction "PTB1_17") (pintype "bidirectional"))
      (node (ref "K2") (pin "24") (pinfunction "PTA2_24") (pintype "bidirectional"))
    )
    (net (code "66") (name "Net-(K2-PTA18)") (class "Default")
      (node (ref "C8") (pin "1") (pinfunction "1_1") (pintype "passive"))
      (node (ref "GND") (pin "1") (pinfunction "1_1") (pintype "passive"))
      (node (ref "K2") (pin "32") (pinfunction "PTA18_32") (pintype "bidirectional"))
    )
    (net (code "67") (name "Net-(K2-PTA19)") (class "Default")
      (node (ref "C11") (pin "1") (pinfunction "1_1") (pintype "passive"))
      (node (ref "GND") (pin "2") (pinfunction "2_2") (pintype "passive"))
      (node (ref "K2") (pin "33") (pinfunction "PTA19_33") (pintype "bidirectional"))
    )
    (net (code "68") (name "Net-(K2-USB0_DM)") (class "Default")
      (node (ref "K2") (pin "6") (pinfunction "USB0_DM_6") (pintype "bidirectional"))
      (node (ref "R6") (pin "2") (pinfunction "2_2") (pintype "passive"))
    )
    (net (code "69") (name "Net-(K2-USB0_DP)") (class "Default")
      (node (ref "K2") (pin "5") (pinfunction "USB0_DP_5") (pintype "bidirectional"))
      (node (ref "R7") (pin "2") (pinfunction "2_2") (pintype "passive"))
    )
    (net (code "70") (name "Net-(K2-VBAT)") (class "Default")
      (node (ref "C3") (pin "1") (pinfunction "1_1") (pintype "passive"))
      (node (ref "K2") (pin "21") (pinfunction "VBAT_21") (pintype "bidirectional"))
      (node (ref "R2") (pin "3") (pinfunction "3_3") (pintype "bidirectional"))
    )
    (net (code "71") (name "Net-(K2-VDDA)") (class "Default")
      (node (ref "C5") (pin "1") (pinfunction "1_1") (pintype "passive"))
      (node (ref "K2") (pin "13") (pinfunction "VDDA_13") (pintype "bidirectional"))
      (node (ref "R4") (pin "1") (pinfunction "1_1") (pintype "passive"))
      (node (ref "R5") (pin "1") (pinfunction "1_1") (pintype "passive"))
    )
    (net (code "72") (name "Net-(K2-VREF_OUT)") (class "Default")
      (node (ref "C17") (pin "1") (pinfunction "1_1") (pintype "passive"))
      (node (ref "K2") (pin "17") (pinfunction "VREF_OUT_17") (pintype "bidirectional"))
    )
    (net (code "73") (name "Net-(LED1-PadC)") (class "Default")
      (node (ref "LED1") (pin "C") (pinfunction "C_C") (pintype "passive"))
      (node (ref "R10") (pin "2") (pinfunction "2_2") (pintype "passive"))
    )
    (net (code "74") (name "Net-(LED2-PadA)") (class "Default")
      (node (ref "LED2") (pin "A") (pinfunction "A_A") (pintype "passive"))
      (node (ref "R15") (pin "1") (pinfunction "1_1") (pintype "passive"))
    )
    (net (code "75") (name "Net-(LED3-PadC)") (class "Default")
      (node (ref "LED3") (pin "C") (pinfunction "C_C") (pintype "passive"))
      (node (ref "R14") (pin "1") (pinfunction "1_1") (pintype "passive"))
    )
    (net (code "76") (name "Net-(LED4-PadC)") (class "Default")
      (node (ref "LED4") (pin "C") (pinfunction "C_C") (pintype "passive"))
      (node (ref "R18") (pin "2") (pinfunction "2_2") (pintype "passive"))
    )
    (net (code "77") (name "Net-(LED5-PadC)") (class "Default")
      (node (ref "LED5") (pin "C") (pinfunction "C_C") (pintype "passive"))
      (node (ref "R22") (pin "2") (pinfunction "2_2") (pintype "passive"))
    )
    (net (code "78") (name "Net-(R21-Pad2)") (class "Default")
      (node (ref "R21") (pin "2") (pinfunction "2_2") (pintype "bidirectional"))
      (node (ref "SJ3") (pin "2") (pinfunction "2_2") (pintype "passive"))
    )
    (net (code "79") (name "Net-(U2-I2S_DIN)") (class "Default")
      (node (ref "SJ1") (pin "1") (pinfunction "1_1") (pintype "passive"))
      (node (ref "U2") (pin "26") (pinfunction "I2S_DIN_26") (pintype "input"))
    )
    (net (code "80") (name "Net-(U2-I2S_DOUT)") (class "Default")
      (node (ref "SJ2") (pin "1") (pinfunction "1_1") (pintype "passive"))
      (node (ref "U2") (pin "25") (pinfunction "I2S_DOUT_25") (pintype "output"))
    )
    (net (code "81") (name "Net-(U2-LINEIN_L)") (class "Default")
      (node (ref "C10") (pin "1") (pinfunction "1_1") (pintype "passive"))
      (node (ref "U2") (pin "14") (pinfunction "LINEIN_L_14") (pintype "input"))
    )
    (net (code "82") (name "Net-(U2-LINEIN_R)") (class "Default")
      (node (ref "C9") (pin "1") (pinfunction "1_1") (pintype "passive"))
      (node (ref "U2") (pin "13") (pinfunction "LINEIN_R_13") (pintype "input"))
    )
    (net (code "83") (name "Net-(U2-LINEOUT_L)") (class "Default")
      (node (ref "C7") (pin "1") (pinfunction "1_1") (pintype "passive"))
      (node (ref "U2") (pin "12") (pinfunction "LINEOUT_L_12") (pintype "output"))
    )
    (net (code "84") (name "Net-(U2-LINEOUT_R)") (class "Default")
      (node (ref "C6") (pin "1") (pinfunction "1_1") (pintype "passive"))
      (node (ref "U2") (pin "11") (pinfunction "LINEOUT_R_11") (pintype "output"))
    )
    (net (code "85") (name "Net-(U2-MIC)") (class "Default")
      (node (ref "C18") (pin "1") (pinfunction "1_1") (pintype "passive"))
      (node (ref "U2") (pin "15") (pinfunction "MIC_15") (pintype "input"))
    )
    (net (code "86") (name "Net-(U2-MIC_BIAS)") (class "Default")
      (node (ref "C20") (pin "1") (pinfunction "1_1") (pintype "passive"))
      (node (ref "R9") (pin "2") (pinfunction "2_2") (pintype "passive"))
      (node (ref "U2") (pin "16") (pinfunction "MIC_BIAS_16") (pintype "passive"))
    )
    (net (code "87") (name "Net-(U2-VAG)") (class "Default")
      (node (ref "C14") (pin "1") (pinfunction "1_1") (pintype "passive"))
      (node (ref "U2") (pin "10") (pinfunction "VAG_10") (pintype "passive"))
    )
    (net (code "88") (name "Net-(U2-VDDA)") (class "Default")
      (node (ref "C19") (pin "1") (pinfunction "1_1") (pintype "passive"))
      (node (ref "R8") (pin "1") (pinfunction "1_1") (pintype "passive"))
      (node (ref "U2") (pin "5") (pinfunction "VDDA_5") (pintype "power_in"))
    )
    (net (code "89") (name "Net-(U2-VDDD)") (class "Default")
      (node (ref "U2") (pin "30") (pinfunction "VDDD_30") (pintype "power_in"))
      (node (ref "U3") (pin "2") (pinfunction "OUT_2") (pintype "output"))
    )
    (net (code "90") (name "Net-(U4-PROG)") (class "Default")
      (node (ref "R19") (pin "2") (pinfunction "2_2") (pintype "passive"))
      (node (ref "U4") (pin "5") (pinfunction "PROG_5") (pintype "input"))
    )
    (net (code "91") (name "Net-(U4-STAT)") (class "Default")
      (node (ref "R14") (pin "2") (pinfunction "2_2") (pintype "passive"))
      (node (ref "R15") (pin "2") (pinfunction "2_2") (pintype "passive"))
      (node (ref "U4") (pin "1") (pinfunction "STAT_1") (pintype "output"))
    )
    (net (code "92") (name "Net-(U4-VBAT)") (class "Default")
      (node (ref "C22") (pin "1") (pinfunction "1_1") (pintype "passive"))
      (node (ref "CN1") (pin "2") (pinfunction "2_2") (pintype "passive"))
      (node (ref "R21") (pin "1") (pinfunction "1_1") (pintype "bidirectional"))
      (node (ref "U4") (pin "3") (pinfunction "VBAT_3") (pintype "power_in"))
    )
    (net (code "93") (name "Net-(U5-PIO2)") (class "Default")
      (node (ref "LED5") (pin "A") (pinfunction "A_A") (pintype "passive"))
      (node (ref "U5") (pin "19") (pinfunction "PIO2_19") (pintype "bidirectional"))
    )
    (net (code "94") (name "Net-(U5-PIO4)") (class "Default")
      (node (ref "JP1") (pin "1") (pinfunction "1_1") (pintype "passive"))
      (node (ref "R20") (pin "2") (pinfunction "2_2") (pintype "passive"))
      (node (ref "U5") (pin "22") (pinfunction "PIO4_22") (pintype "bidirectional"))
    )
    (net (code "95") (name "Net-(U5-PIO5)") (class "Default")
      (node (ref "LED4") (pin "A") (pinfunction "A_A") (pintype "passive"))
      (node (ref "U5") (pin "21") (pinfunction "PIO5_21") (pintype "bidirectional"))
    )
    (net (code "96") (name "VIN") (class "Default")
      (node (ref "C4") (pin "1") (pinfunction "1_1") (pintype "passive"))
      (node (ref "J2") (pin "4") (pinfunction "4_4") (pintype "passive"))
      (node (ref "J5") (pin "14") (pinfunction "14_14") (pintype "passive"))
      (node (ref "J6") (pin "14") (pinfunction "14_14") (pintype "passive"))
      (node (ref "R13") (pin "1") (pinfunction "1_1") (pintype "passive"))
      (node (ref "R21") (pin "3") (pinfunction "3_3") (pintype "bidirectional"))
      (node (ref "T1") (pin "1") (pinfunction "IN_1") (pintype "bidirectional"))
      (node (ref "U3") (pin "1") (pinfunction "IN_1") (pintype "input"))
    )
    (net (code "97") (name "V_USB") (class "Default")
      (node (ref "C1") (pin "1") (pinfunction "1_1") (pintype "passive"))
      (node (ref "C21") (pin "1") (pinfunction "1_1") (pintype "passive"))
      (node (ref "J5") (pin "1") (pinfunction "1_1") (pintype "passive"))
      (node (ref "J8") (pin "VBUS") (pinfunction "VBUS_VBUS") (pintype "power_in"))
      (node (ref "LED3") (pin "A") (pinfunction "A_A") (pintype "passive"))
      (node (ref "SJ3") (pin "1") (pinfunction "1_1") (pintype "passive"))
      (node (ref "U4") (pin "4") (pinfunction "VDD_4") (pintype "power_in"))
    )
    (net (code "98") (name "unconnected-(J3-PadRING2)") (class "Default")
      (node (ref "J3") (pin "RING2") (pinfunction "RING2_RING2") (pintype "bidirectional"))
    )
    (net (code "99") (name "unconnected-(K1-PTA0-Pad30)") (class "Default")
      (node (ref "K1") (pin "30") (pinfunction "PTA0_30") (pintype "bidirectional"))
    )
    (net (code "100") (name "unconnected-(K1-PTA1-Pad31)") (class "Default")
      (node (ref "K1") (pin "31") (pinfunction "PTA1_31") (pintype "bidirectional"))
    )
    (net (code "101") (name "unconnected-(K1-PTA2-Pad32)") (class "Default")
      (node (ref "K1") (pin "32") (pinfunction "PTA2_32") (pintype "bidirectional"))
    )
    (net (code "102") (name "unconnected-(K1-PTA3-Pad7)") (class "Default")
      (node (ref "K1") (pin "7") (pinfunction "PTA3_7") (pintype "bidirectional"))
    )
    (net (code "103") (name "unconnected-(K1-PTA5-Pad9)") (class "Default")
      (node (ref "K1") (pin "9") (pinfunction "PTA5_9") (pintype "bidirectional"))
    )
    (net (code "104") (name "unconnected-(K1-PTB3-Pad23)") (class "Default")
      (node (ref "K1") (pin "23") (pinfunction "PTB3_23") (pintype "bidirectional"))
    )
    (net (code "105") (name "unconnected-(K1-PTB4-Pad24)") (class "Default")
      (node (ref "K1") (pin "24") (pinfunction "PTB4_24") (pintype "bidirectional"))
    )
    (net (code "106") (name "unconnected-(K2-EXTAL32-Pad20)") (class "Default")
      (node (ref "K2") (pin "20") (pinfunction "EXTAL32_20") (pintype "bidirectional"))
    )
    (net (code "107") (name "unconnected-(K2-VREGIN-Pad8)") (class "Default")
      (node (ref "K2") (pin "8") (pinfunction "VREGIN_8") (pintype "bidirectional"))
    )
    (net (code "108") (name "unconnected-(K2-XTAL32-Pad19)") (class "Default")
      (node (ref "K2") (pin "19") (pinfunction "XTAL32_19") (pintype "bidirectional"))
    )
    (net (code "109") (name "unconnected-(U1-NC-Pad1)") (class "Default")
      (node (ref "U1") (pin "1") (pinfunction "NC_1") (pintype "bidirectional"))
    )
    (net (code "110") (name "unconnected-(U1-PadCD1)") (class "Default")
      (node (ref "U1") (pin "CD1") (pinfunction "CD1_CD1") (pintype "bidirectional"))
    )
    (net (code "111") (name "unconnected-(U1-RSV-Pad8)") (class "Default")
      (node (ref "U1") (pin "8") (pinfunction "RSV_8") (pintype "bidirectional"))
    )
    (net (code "112") (name "unconnected-(U2-CPFLT-Pad18)") (class "Default")
      (node (ref "U2") (pin "18") (pinfunction "CPFLT_18") (pintype "passive"))
    )
    (net (code "113") (name "unconnected-(U2-NC-Pad28)") (class "Default")
      (node (ref "U2") (pin "28") (pinfunction "NC_28") (pintype "passive"))
    )
    (net (code "114") (name "unconnected-(U2-NC_2-Pad8)") (class "Default")
      (node (ref "U2") (pin "8") (pinfunction "NC_2_8") (pintype "passive"))
    )
    (net (code "115") (name "unconnected-(U2-NC_3-Pad9)") (class "Default")
      (node (ref "U2") (pin "9") (pinfunction "NC_3_9") (pintype "passive"))
    )
    (net (code "116") (name "unconnected-(U2-NC_4-Pad17)") (class "Default")
      (node (ref "U2") (pin "17") (pinfunction "NC_4_17") (pintype "passive"))
    )
    (net (code "117") (name "unconnected-(U2-NC_5-Pad19)") (class "Default")
      (node (ref "U2") (pin "19") (pinfunction "NC_5_19") (pintype "passive"))
    )
    (net (code "118") (name "unconnected-(U2-NC_6-Pad22)") (class "Default")
      (node (ref "U2") (pin "22") (pinfunction "NC_6_22") (pintype "passive"))
    )
    (net (code "119") (name "unconnected-(U5-AIO1-Pad35)") (class "Default")
      (node (ref "U5") (pin "35") (pinfunction "AIO1_35") (pintype "bidirectional"))
    )
    (net (code "120") (name "unconnected-(U5-AIO2-Pad30)") (class "Default")
      (node (ref "U5") (pin "30") (pinfunction "AIO2_30") (pintype "bidirectional"))
    )
    (net (code "121") (name "unconnected-(U5-NC-Pad26)") (class "Default")
      (node (ref "U5") (pin "26") (pinfunction "NC_26") (pintype "bidirectional"))
    )
    (net (code "122") (name "unconnected-(U5-PCMCLK-Pad7)") (class "Default")
      (node (ref "U5") (pin "7") (pinfunction "PCMCLK_7") (pintype "bidirectional"))
    )
    (net (code "123") (name "unconnected-(U5-PCMIN-Pad9)") (class "Default")
      (node (ref "U5") (pin "9") (pinfunction "PCMIN_9") (pintype "bidirectional"))
    )
    (net (code "124") (name "unconnected-(U5-PCMOUT-Pad10)") (class "Default")
      (node (ref "U5") (pin "10") (pinfunction "PCMOUT_10") (pintype "bidirectional"))
    )
    (net (code "125") (name "unconnected-(U5-PCMSYNC-Pad8)") (class "Default")
      (node (ref "U5") (pin "8") (pinfunction "PCMSYNC_8") (pintype "bidirectional"))
    )
    (net (code "126") (name "unconnected-(U5-PIO3-Pad20)") (class "Default")
      (node (ref "U5") (pin "20") (pinfunction "PIO3_20") (pintype "bidirectional"))
    )
    (net (code "127") (name "unconnected-(U5-PIO6-Pad3)") (class "Default")
      (node (ref "U5") (pin "3") (pinfunction "PIO6_3") (pintype "bidirectional"))
    )
    (net (code "128") (name "unconnected-(U5-PIO7-Pad4)") (class "Default")
      (node (ref "U5") (pin "4") (pinfunction "PIO7_4") (pintype "bidirectional"))
    )
    (net (code "129") (name "unconnected-(U5-PIO8-Pad34)") (class "Default")
      (node (ref "U5") (pin "34") (pinfunction "PIO8_34") (pintype "bidirectional"))
    )
    (net (code "130") (name "unconnected-(U5-PIO9-Pad33)") (class "Default")
      (node (ref "U5") (pin "33") (pinfunction "PIO9_33") (pintype "bidirectional"))
    )
    (net (code "131") (name "unconnected-(U5-PIO10-Pad32)") (class "Default")
      (node (ref "U5") (pin "32") (pinfunction "PIO10_32") (pintype "bidirectional"))
    )
    (net (code "132") (name "unconnected-(U5-PIO11-Pad31)") (class "Default")
      (node (ref "U5") (pin "31") (pinfunction "PIO11_31") (pintype "bidirectional"))
    )
    (net (code "133") (name "unconnected-(U5-RESET-Pad5)") (class "Default")
      (node (ref "U5") (pin "5") (pinfunction "RESET_5") (pintype "bidirectional"))
    )
    (net (code "134") (name "unconnected-(U5-SPICLK-Pad6)") (class "Default")
      (node (ref "U5") (pin "6") (pinfunction "SPICLK_6") (pintype "bidirectional"))
    )
    (net (code "135") (name "unconnected-(U5-SPICSB-Pad23)") (class "Default")
      (node (ref "U5") (pin "23") (pinfunction "SPICSB_23") (pintype "bidirectional"))
    )
    (net (code "136") (name "unconnected-(U5-SPIMISO-Pad24)") (class "Default")
      (node (ref "U5") (pin "24") (pinfunction "SPIMISO_24") (pintype "bidirectional"))
    )
    (net (code "137") (name "unconnected-(U5-SPIMOSI-Pad2)") (class "Default")
      (node (ref "U5") (pin "2") (pinfunction "SPIMOSI_2") (pintype "bidirectional"))
    )
    (net (code "138") (name "unconnected-(U5-USBD+-Pad17)") (class "Default")
      (node (ref "U5") (pin "17") (pinfunction "USBD+_17") (pintype "bidirectional"))
    )
    (net (code "139") (name "unconnected-(U5-USBD--Pad18)") (class "Default")
      (node (ref "U5") (pin "18") (pinfunction "USBD-_18") (pintype "bidirectional"))
    )
  )
)
